# waterpump.net
KiCad netlist of a schematic drawn in Altium Designer
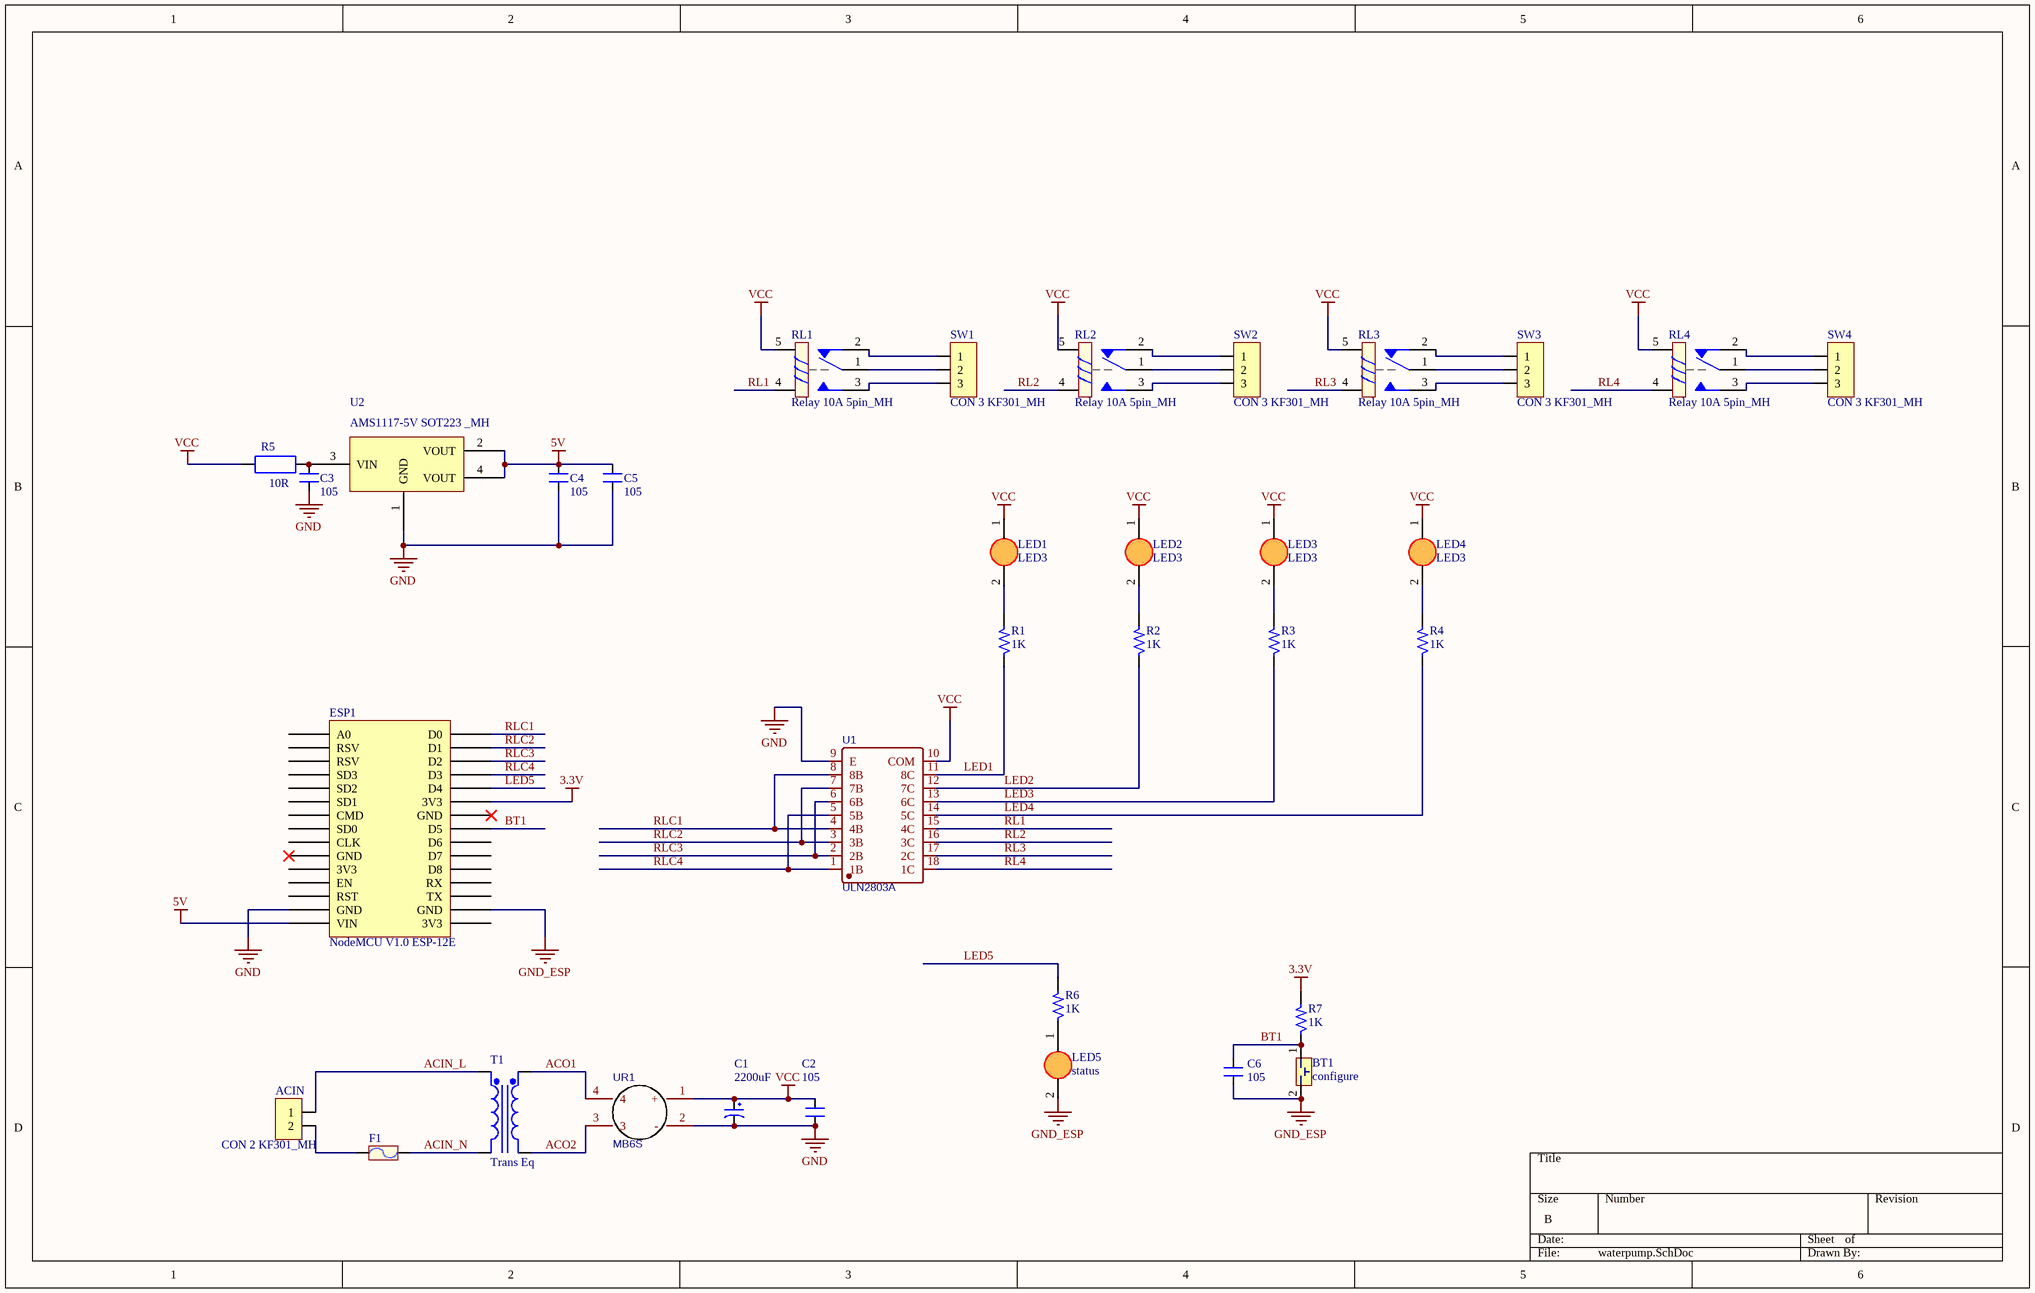
[diagram p0: waterpump.SchDoc]

(export (version "E")
  (design (tool "Eeschema 10.0.6"))
  (components
    (comp (ref "ACIN")
      (value "CON 2 KF301_MH")
      (footprint "CON 2 KF301")
      (description "CON 2 KF301, 5.08mm")
      (libsource (lib "MH_DA_THU_VIEN_16122016") (part "CON 2 KF301_MH"))
    )
    (comp (ref "BT1")
      (value "configure")
      (footprint "BUTTON 4P SMD")
      (description "Nút nhấn 4 chân, dán")
      (libsource (lib "MH_DA_THU_VIEN_16122016") (part "BUTTON 4P SMD_MH"))
    )
    (comp (ref "C1")
      (value "2200uF")
      (footprint "CP3/7")
      (description "2200uF_25V")
      (libsource (lib "MH_DA_THU_VIEN_16122016") (part "TU_HOA_2200uF_25V_MH"))
    )
    (comp (ref "C2")
      (value "105")
      (footprint "0805_HV")
      (description "Cap SMD")
      (libsource (lib "hatcatbietbay") (part "CM"))
    )
    (comp (ref "C3")
      (value "105")
      (footprint "0805_HV")
      (description "Cap SMD")
      (libsource (lib "hatcatbietbay") (part "CM"))
    )
    (comp (ref "C4")
      (value "105")
      (footprint "0805_HV")
      (description "Cap SMD")
      (libsource (lib "hatcatbietbay") (part "CM"))
    )
    (comp (ref "C5")
      (value "105")
      (footprint "0805_HV")
      (description "Cap SMD")
      (libsource (lib "hatcatbietbay") (part "CM"))
    )
    (comp (ref "C6")
      (value "105")
      (footprint "0805_HV")
      (description "Cap SMD")
      (libsource (lib "hatcatbietbay") (part "CM"))
    )
    (comp (ref "ESP1")
      (value "NodeMCU V1.0 ESP-12E")
      (footprint "ESP-8266")
      (description "NodeMCU V1.0 ESP8266 (ESP-12E)")
      (libsource (lib "nodemcu") (part "NodeMCU V1.0 ESP-12E"))
    )
    (comp (ref "F1")
      (value "FUSE_AUTO_0.5A 8V 1206_MH")
      (footprint "FUSE 1206")
      (description "Fuse")
      (libsource (lib "MH_DA_THU_VIEN_16122016") (part "FUSE_AUTO_0.5A 8V 1206_MH"))
    )
    (comp (ref "LED1")
      (value "LED3")
      (footprint "LED 3mm Do")
      (description "LED 3mm")
      (libsource (lib "MH_DA_THU_VIEN_16122016") (part "LED 3mm_MH"))
    )
    (comp (ref "LED2")
      (value "LED3")
      (footprint "LED 3mm Do")
      (description "LED 3mm")
      (libsource (lib "MH_DA_THU_VIEN_16122016") (part "LED 3mm_MH"))
    )
    (comp (ref "LED3")
      (value "LED3")
      (footprint "LED 3mm Do")
      (description "LED 3mm")
      (libsource (lib "MH_DA_THU_VIEN_16122016") (part "LED 3mm_MH"))
    )
    (comp (ref "LED4")
      (value "LED3")
      (footprint "LED 3mm Do")
      (description "LED 3mm")
      (libsource (lib "MH_DA_THU_VIEN_16122016") (part "LED 3mm_MH"))
    )
    (comp (ref "LED5")
      (value "status")
      (footprint "LED_0805")
      (description "LED 3mm")
      (libsource (lib "MH_DA_THU_VIEN_16122016") (part "LED SMD_0805_MH"))
    )
    (comp (ref "R1")
      (value "1K")
      (footprint "0805_HV")
      (description "Resistor 1/4W")
      (libsource (lib "hatcatbietbay") (part "R"))
    )
    (comp (ref "R2")
      (value "1K")
      (footprint "0805_HV")
      (description "Resistor 1/4W")
      (libsource (lib "hatcatbietbay") (part "R"))
    )
    (comp (ref "R3")
      (value "1K")
      (footprint "0805_HV")
      (description "Resistor 1/4W")
      (libsource (lib "hatcatbietbay") (part "R"))
    )
    (comp (ref "R4")
      (value "1K")
      (footprint "0805_HV")
      (description "Resistor 1/4W")
      (libsource (lib "hatcatbietbay") (part "R"))
    )
    (comp (ref "R5")
      (value "10R")
      (footprint "TRO_VACH_2W")
      (libsource (lib "MH_DA_THU_VIEN_16122016") (part "TRO_CS_2W_MH"))
    )
    (comp (ref "R6")
      (value "1K")
      (footprint "0805_HV")
      (description "Resistor 1/4W")
      (libsource (lib "hatcatbietbay") (part "R"))
    )
    (comp (ref "R7")
      (value "1K")
      (footprint "0805_HV")
      (description "Resistor 1/4W")
      (libsource (lib "hatcatbietbay") (part "R"))
    )
    (comp (ref "RL1")
      (value "Relay 10A 5pin_MH")
      (footprint "relay 10A 5pin")
      (description "Relay")
      (libsource (lib "MH_DA_THU_VIEN_16122016") (part "Relay 10A 5pin_MH"))
    )
    (comp (ref "RL2")
      (value "Relay 10A 5pin_MH")
      (footprint "relay 10A 5pin")
      (description "Relay")
      (libsource (lib "MH_DA_THU_VIEN_16122016") (part "Relay 10A 5pin_MH"))
    )
    (comp (ref "RL3")
      (value "Relay 10A 5pin_MH")
      (footprint "relay 10A 5pin")
      (description "Relay")
      (libsource (lib "MH_DA_THU_VIEN_16122016") (part "Relay 10A 5pin_MH"))
    )
    (comp (ref "RL4")
      (value "Relay 10A 5pin_MH")
      (footprint "relay 10A 5pin")
      (description "Relay")
      (libsource (lib "MH_DA_THU_VIEN_16122016") (part "Relay 10A 5pin_MH"))
    )
    (comp (ref "SW1")
      (value "CON 3 KF301_MH")
      (footprint "CON 3 KF301")
      (description "CON 3 KF301, 5.08mm")
      (libsource (lib "MH_DA_THU_VIEN_16122016") (part "CON 3 KF301_MH"))
    )
    (comp (ref "SW2")
      (value "CON 3 KF301_MH")
      (footprint "CON 3 KF301")
      (description "CON 3 KF301, 5.08mm")
      (libsource (lib "MH_DA_THU_VIEN_16122016") (part "CON 3 KF301_MH"))
    )
    (comp (ref "SW3")
      (value "CON 3 KF301_MH")
      (footprint "CON 3 KF301")
      (description "CON 3 KF301, 5.08mm")
      (libsource (lib "MH_DA_THU_VIEN_16122016") (part "CON 3 KF301_MH"))
    )
    (comp (ref "SW4")
      (value "CON 3 KF301_MH")
      (footprint "CON 3 KF301")
      (description "CON 3 KF301, 5.08mm")
      (libsource (lib "MH_DA_THU_VIEN_16122016") (part "CON 3 KF301_MH"))
    )
    (comp (ref "T1")
      (value "Trans Eq")
      (footprint "AS3010")
      (description "Transformer (Equivalent Circuit Model)")
      (fields (field (name "PUBLISHER") "Altium Limited"))
      (libsource (lib "Schlib1") (part "Trans Eq"))
    )
    (comp (ref "U1")
      (value "ULN2803A")
      (footprint "SOIC-18_300MIL")
      (fields (field (name "BOM_SUPPLIER PART") "C181731") (field (name "CONTRIBUTOR") "LCSC"))
      (libsource (lib "Schlib1") (part "ULN2803A"))
    )
    (comp (ref "U2")
      (value "AMS1117-5V SOT223 _MH")
      (footprint "SOT223")
      (description "AMS1117-3.3V SOT223 _MH")
      (libsource (lib "MH_DA_THU_VIEN_16122016") (part "AMS1117-3.3V SOT223 _MH"))
    )
    (comp (ref "UR1")
      (value "MB6S")
      (footprint "MB6S")
      (fields (field (name "BOM_SUPPLIER PART") "C83964"))
      (libsource (lib "Schlib1") (part "MB6S"))
    )
  )
  (nets
    (net (code "1") (name "/ACIN_L") (class "Default")
      (node (ref "ACIN") (pin "1") (pinfunction "1_1") (pintype "passive"))
      (node (ref "T1") (pin "1") (pinfunction "Pri+_1") (pintype "passive"))
    )
    (net (code "2") (name "/ACIN_N") (class "Default")
      (node (ref "F1") (pin "2") (pinfunction "2_2") (pintype "passive"))
      (node (ref "T1") (pin "2") (pinfunction "Pri-_2") (pintype "passive"))
    )
    (net (code "3") (name "/ACO1") (class "Default")
      (node (ref "T1") (pin "3") (pinfunction "Sec+_3") (pintype "passive"))
      (node (ref "UR1") (pin "4") (pinfunction "4_4") (pintype "passive"))
    )
    (net (code "4") (name "/ACO2") (class "Default")
      (node (ref "T1") (pin "4") (pinfunction "Sec-_4") (pintype "passive"))
      (node (ref "UR1") (pin "3") (pinfunction "3_3") (pintype "passive"))
    )
    (net (code "5") (name "/BT1") (class "Default")
      (node (ref "BT1") (pin "1") (pinfunction "1_1") (pintype "passive"))
      (node (ref "C6") (pin "2") (pinfunction "2_2") (pintype "passive"))
      (node (ref "ESP1") (pin "D5") (pinfunction "D5_D5") (pintype "passive"))
      (node (ref "R7") (pin "1") (pinfunction "1_1") (pintype "passive"))
    )
    (net (code "6") (name "/LED1") (class "Default")
      (node (ref "R1") (pin "1") (pinfunction "1_1") (pintype "passive"))
      (node (ref "U1") (pin "11") (pinfunction "8C_11") (pintype "passive"))
    )
    (net (code "7") (name "/LED2") (class "Default")
      (node (ref "R2") (pin "1") (pinfunction "1_1") (pintype "passive"))
      (node (ref "U1") (pin "12") (pinfunction "7C_12") (pintype "passive"))
    )
    (net (code "8") (name "/LED3") (class "Default")
      (node (ref "R3") (pin "1") (pinfunction "1_1") (pintype "passive"))
      (node (ref "U1") (pin "13") (pinfunction "6C_13") (pintype "passive"))
    )
    (net (code "9") (name "/LED4") (class "Default")
      (node (ref "R4") (pin "1") (pinfunction "1_1") (pintype "passive"))
      (node (ref "U1") (pin "14") (pinfunction "5C_14") (pintype "passive"))
    )
    (net (code "10") (name "/LED5") (class "Default")
      (node (ref "ESP1") (pin "D4") (pinfunction "D4_D4") (pintype "passive"))
      (node (ref "R6") (pin "2") (pinfunction "2_2") (pintype "passive"))
    )
    (net (code "11") (name "/RL1") (class "Default")
      (node (ref "RL1") (pin "4") (pinfunction "4_4") (pintype "passive"))
      (node (ref "U1") (pin "15") (pinfunction "4C_15") (pintype "passive"))
    )
    (net (code "12") (name "/RL2") (class "Default")
      (node (ref "RL2") (pin "4") (pinfunction "4_4") (pintype "passive"))
      (node (ref "U1") (pin "16") (pinfunction "3C_16") (pintype "passive"))
    )
    (net (code "13") (name "/RL3") (class "Default")
      (node (ref "RL3") (pin "4") (pinfunction "4_4") (pintype "passive"))
      (node (ref "U1") (pin "17") (pinfunction "2C_17") (pintype "passive"))
    )
    (net (code "14") (name "/RL4") (class "Default")
      (node (ref "RL4") (pin "4") (pinfunction "4_4") (pintype "passive"))
      (node (ref "U1") (pin "18") (pinfunction "1C_18") (pintype "passive"))
    )
    (net (code "15") (name "/RLC1") (class "Default")
      (node (ref "ESP1") (pin "D0") (pinfunction "D0_D0") (pintype "passive"))
      (node (ref "U1") (pin "4") (pinfunction "4B_4") (pintype "passive"))
      (node (ref "U1") (pin "8") (pinfunction "8B_8") (pintype "passive"))
    )
    (net (code "16") (name "/RLC2") (class "Default")
      (node (ref "ESP1") (pin "D1") (pinfunction "D1_D1") (pintype "passive"))
      (node (ref "U1") (pin "3") (pinfunction "3B_3") (pintype "passive"))
      (node (ref "U1") (pin "7") (pinfunction "7B_7") (pintype "passive"))
    )
    (net (code "17") (name "/RLC3") (class "Default")
      (node (ref "ESP1") (pin "D2") (pinfunction "D2_D2") (pintype "passive"))
      (node (ref "U1") (pin "2") (pinfunction "2B_2") (pintype "passive"))
      (node (ref "U1") (pin "6") (pinfunction "6B_6") (pintype "passive"))
    )
    (net (code "18") (name "/RLC4") (class "Default")
      (node (ref "ESP1") (pin "D3") (pinfunction "D3_D3") (pintype "passive"))
      (node (ref "U1") (pin "1") (pinfunction "1B_1") (pintype "passive"))
      (node (ref "U1") (pin "5") (pinfunction "5B_5") (pintype "passive"))
    )
    (net (code "19") (name "3.3V") (class "Default")
      (node (ref "ESP1") (pin "3V3") (pinfunction "3V3_3V3") (pintype "passive"))
      (node (ref "R7") (pin "2") (pinfunction "2_2") (pintype "passive"))
    )
    (net (code "20") (name "5V") (class "Default")
      (node (ref "C4") (pin "2") (pinfunction "2_2") (pintype "passive"))
      (node (ref "C5") (pin "2") (pinfunction "2_2") (pintype "passive"))
      (node (ref "ESP1") (pin "VIN") (pinfunction "VIN_VIN") (pintype "passive"))
      (node (ref "U2") (pin "2") (pinfunction "VOUT_2") (pintype "passive"))
      (node (ref "U2") (pin "4") (pinfunction "VOUT_4") (pintype "passive"))
    )
    (net (code "21") (name "GND") (class "Default")
      (node (ref "C1") (pin "2") (pinfunction "2_2") (pintype "passive"))
      (node (ref "C2") (pin "1") (pinfunction "1_1") (pintype "passive"))
      (node (ref "C3") (pin "1") (pinfunction "1_1") (pintype "passive"))
      (node (ref "C4") (pin "1") (pinfunction "1_1") (pintype "passive"))
      (node (ref "C5") (pin "1") (pinfunction "1_1") (pintype "passive"))
      (node (ref "ESP1") (pin "GND") (pinfunction "GND_GND") (pintype "passive"))
      (node (ref "U1") (pin "9") (pinfunction "E_9") (pintype "passive"))
      (node (ref "U2") (pin "1") (pinfunction "GND_1") (pintype "passive"))
      (node (ref "UR1") (pin "2") (pinfunction "-_2") (pintype "passive"))
    )
    (net (code "22") (name "GND_ESP") (class "Default")
      (node (ref "BT1") (pin "2") (pinfunction "2_2") (pintype "passive"))
      (node (ref "C6") (pin "1") (pinfunction "1_1") (pintype "passive"))
      (node (ref "ESP1") (pin "GND") (pinfunction "GND_GND") (pintype "passive"))
      (node (ref "LED5") (pin "2") (pinfunction "K_2") (pintype "passive"))
    )
    (net (code "23") (name "Net-(ACIN-Pad2)") (class "Default")
      (node (ref "ACIN") (pin "2") (pinfunction "2_2") (pintype "passive"))
      (node (ref "F1") (pin "1") (pinfunction "1_1") (pintype "passive"))
    )
    (net (code "24") (name "Net-(LED1-K)") (class "Default")
      (node (ref "LED1") (pin "2") (pinfunction "K_2") (pintype "passive"))
      (node (ref "R1") (pin "2") (pinfunction "2_2") (pintype "passive"))
    )
    (net (code "25") (name "Net-(LED2-K)") (class "Default")
      (node (ref "LED2") (pin "2") (pinfunction "K_2") (pintype "passive"))
      (node (ref "R2") (pin "2") (pinfunction "2_2") (pintype "passive"))
    )
    (net (code "26") (name "Net-(LED3-K)") (class "Default")
      (node (ref "LED3") (pin "2") (pinfunction "K_2") (pintype "passive"))
      (node (ref "R3") (pin "2") (pinfunction "2_2") (pintype "passive"))
    )
    (net (code "27") (name "Net-(LED4-K)") (class "Default")
      (node (ref "LED4") (pin "2") (pinfunction "K_2") (pintype "passive"))
      (node (ref "R4") (pin "2") (pinfunction "2_2") (pintype "passive"))
    )
    (net (code "28") (name "Net-(LED5-A)") (class "Default")
      (node (ref "LED5") (pin "1") (pinfunction "A_1") (pintype "passive"))
      (node (ref "R6") (pin "1") (pinfunction "1_1") (pintype "passive"))
    )
    (net (code "29") (name "Net-(RL1-Pad1)") (class "Default")
      (node (ref "RL1") (pin "1") (pinfunction "1_1") (pintype "passive"))
      (node (ref "SW1") (pin "2") (pinfunction "2_2") (pintype "passive"))
    )
    (net (code "30") (name "Net-(RL1-Pad2)") (class "Default")
      (node (ref "RL1") (pin "2") (pinfunction "2_2") (pintype "passive"))
      (node (ref "SW1") (pin "1") (pinfunction "1_1") (pintype "passive"))
    )
    (net (code "31") (name "Net-(RL1-Pad3)") (class "Default")
      (node (ref "RL1") (pin "3") (pinfunction "3_3") (pintype "passive"))
      (node (ref "SW1") (pin "3") (pinfunction "3_3") (pintype "passive"))
    )
    (net (code "32") (name "Net-(RL2-Pad1)") (class "Default")
      (node (ref "RL2") (pin "1") (pinfunction "1_1") (pintype "passive"))
      (node (ref "SW2") (pin "2") (pinfunction "2_2") (pintype "passive"))
    )
    (net (code "33") (name "Net-(RL2-Pad2)") (class "Default")
      (node (ref "RL2") (pin "2") (pinfunction "2_2") (pintype "passive"))
      (node (ref "SW2") (pin "1") (pinfunction "1_1") (pintype "passive"))
    )
    (net (code "34") (name "Net-(RL2-Pad3)") (class "Default")
      (node (ref "RL2") (pin "3") (pinfunction "3_3") (pintype "passive"))
      (node (ref "SW2") (pin "3") (pinfunction "3_3") (pintype "passive"))
    )
    (net (code "35") (name "Net-(RL3-Pad1)") (class "Default")
      (node (ref "RL3") (pin "1") (pinfunction "1_1") (pintype "passive"))
      (node (ref "SW3") (pin "2") (pinfunction "2_2") (pintype "passive"))
    )
    (net (code "36") (name "Net-(RL3-Pad2)") (class "Default")
      (node (ref "RL3") (pin "2") (pinfunction "2_2") (pintype "passive"))
      (node (ref "SW3") (pin "1") (pinfunction "1_1") (pintype "passive"))
    )
    (net (code "37") (name "Net-(RL3-Pad3)") (class "Default")
      (node (ref "RL3") (pin "3") (pinfunction "3_3") (pintype "passive"))
      (node (ref "SW3") (pin "3") (pinfunction "3_3") (pintype "passive"))
    )
    (net (code "38") (name "Net-(RL4-Pad1)") (class "Default")
      (node (ref "RL4") (pin "1") (pinfunction "1_1") (pintype "passive"))
      (node (ref "SW4") (pin "2") (pinfunction "2_2") (pintype "passive"))
    )
    (net (code "39") (name "Net-(RL4-Pad2)") (class "Default")
      (node (ref "RL4") (pin "2") (pinfunction "2_2") (pintype "passive"))
      (node (ref "SW4") (pin "1") (pinfunction "1_1") (pintype "passive"))
    )
    (net (code "40") (name "Net-(RL4-Pad3)") (class "Default")
      (node (ref "RL4") (pin "3") (pinfunction "3_3") (pintype "passive"))
      (node (ref "SW4") (pin "3") (pinfunction "3_3") (pintype "passive"))
    )
    (net (code "41") (name "Net-(U2-VIN)") (class "Default")
      (node (ref "C3") (pin "2") (pinfunction "2_2") (pintype "passive"))
      (node (ref "R5") (pin "2") (pinfunction "2_2") (pintype "passive"))
      (node (ref "U2") (pin "3") (pinfunction "VIN_3") (pintype "passive"))
    )
    (net (code "42") (name "VCC") (class "Default")
      (node (ref "C1") (pin "1") (pinfunction "1_1") (pintype "passive"))
      (node (ref "C2") (pin "2") (pinfunction "2_2") (pintype "passive"))
      (node (ref "LED1") (pin "1") (pinfunction "A_1") (pintype "passive"))
      (node (ref "LED2") (pin "1") (pinfunction "A_1") (pintype "passive"))
      (node (ref "LED3") (pin "1") (pinfunction "A_1") (pintype "passive"))
      (node (ref "LED4") (pin "1") (pinfunction "A_1") (pintype "passive"))
      (node (ref "R5") (pin "1") (pinfunction "1_1") (pintype "passive"))
      (node (ref "RL1") (pin "5") (pinfunction "5_5") (pintype "passive"))
      (node (ref "RL2") (pin "5") (pinfunction "5_5") (pintype "passive"))
      (node (ref "RL3") (pin "5") (pinfunction "5_5") (pintype "passive"))
      (node (ref "RL4") (pin "5") (pinfunction "5_5") (pintype "passive"))
      (node (ref "U1") (pin "10") (pinfunction "COM_10") (pintype "passive"))
      (node (ref "UR1") (pin "1") (pinfunction "+_1") (pintype "passive"))
    )
    (net (code "43") (name "unconnected-(ESP1-Pad3V3)") (class "Default")
      (node (ref "ESP1") (pin "3V3") (pinfunction "3V3_3V3") (pintype "passive"))
    )
    (net (code "44") (name "unconnected-(ESP1-Pad3V3)_1") (class "Default")
      (node (ref "ESP1") (pin "3V3") (pinfunction "3V3_3V3") (pintype "passive"))
    )
    (net (code "45") (name "unconnected-(ESP1-PadA0)") (class "Default")
      (node (ref "ESP1") (pin "A0") (pinfunction "A0_A0") (pintype "passive"))
    )
    (net (code "46") (name "unconnected-(ESP1-PadCLK)") (class "Default")
      (node (ref "ESP1") (pin "CLK") (pinfunction "CLK_CLK") (pintype "passive"))
    )
    (net (code "47") (name "unconnected-(ESP1-PadCMD)") (class "Default")
      (node (ref "ESP1") (pin "CMD") (pinfunction "CMD_CMD") (pintype "passive"))
    )
    (net (code "48") (name "unconnected-(ESP1-PadD6)") (class "Default")
      (node (ref "ESP1") (pin "D6") (pinfunction "D6_D6") (pintype "passive"))
    )
    (net (code "49") (name "unconnected-(ESP1-PadD7)") (class "Default")
      (node (ref "ESP1") (pin "D7") (pinfunction "D7_D7") (pintype "passive"))
    )
    (net (code "50") (name "unconnected-(ESP1-PadD8)") (class "Default")
      (node (ref "ESP1") (pin "D8") (pinfunction "D8_D8") (pintype "passive"))
    )
    (net (code "51") (name "unconnected-(ESP1-PadEN)") (class "Default")
      (node (ref "ESP1") (pin "EN") (pinfunction "EN_EN") (pintype "passive"))
    )
    (net (code "52") (name "unconnected-(ESP1-PadGND)") (class "Default")
      (node (ref "ESP1") (pin "GND") (pinfunction "GND_GND") (pintype "passive+no_connect"))
    )
    (net (code "53") (name "unconnected-(ESP1-PadGND)_1") (class "Default")
      (node (ref "ESP1") (pin "GND") (pinfunction "GND_GND") (pintype "passive+no_connect"))
    )
    (net (code "54") (name "unconnected-(ESP1-PadRST)") (class "Default")
      (node (ref "ESP1") (pin "RST") (pinfunction "RST_RST") (pintype "passive"))
    )
    (net (code "55") (name "unconnected-(ESP1-PadRSV)") (class "Default")
      (node (ref "ESP1") (pin "RSV") (pinfunction "RSV_RSV") (pintype "passive"))
    )
    (net (code "56") (name "unconnected-(ESP1-PadRSV)_1") (class "Default")
      (node (ref "ESP1") (pin "RSV") (pinfunction "RSV_RSV") (pintype "passive"))
    )
    (net (code "57") (name "unconnected-(ESP1-PadRX)") (class "Default")
      (node (ref "ESP1") (pin "RX") (pinfunction "RX_RX") (pintype "passive"))
    )
    (net (code "58") (name "unconnected-(ESP1-PadSD0)") (class "Default")
      (node (ref "ESP1") (pin "SD0") (pinfunction "SD0_SD0") (pintype "passive"))
    )
    (net (code "59") (name "unconnected-(ESP1-PadSD1)") (class "Default")
      (node (ref "ESP1") (pin "SD1") (pinfunction "SD1_SD1") (pintype "passive"))
    )
    (net (code "60") (name "unconnected-(ESP1-PadSD2)") (class "Default")
      (node (ref "ESP1") (pin "SD2") (pinfunction "SD2_SD2") (pintype "passive"))
    )
    (net (code "61") (name "unconnected-(ESP1-PadSD3)") (class "Default")
      (node (ref "ESP1") (pin "SD3") (pinfunction "SD3_SD3") (pintype "passive"))
    )
    (net (code "62") (name "unconnected-(ESP1-PadTX)") (class "Default")
      (node (ref "ESP1") (pin "TX") (pinfunction "TX_TX") (pintype "passive"))
    )
  )
)
